# pads.net
KiCad netlist of a schematic drawn in EAGLE
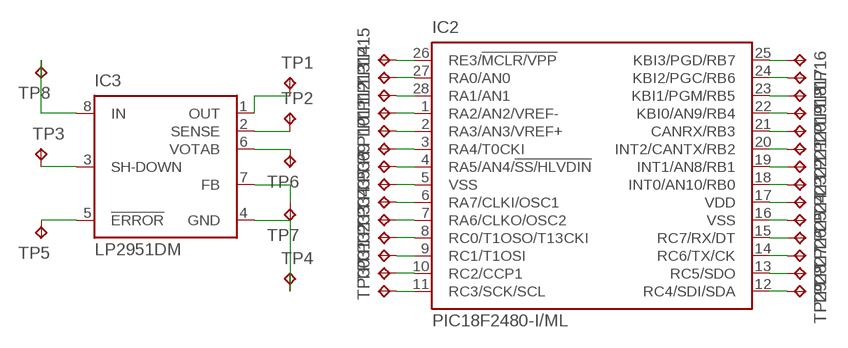
[diagram p0: schematic, sheet 1]

(export (version "E")
  (design (tool "Eeschema 10.0.6"))
  (components
    (comp (ref "IC2")
      (value "PIC18F2480-I/ML")
      (footprint "eagle-import:QFN28-ML_6X6MM")
      (fields (field (name "MF") "MICROCHIP"))
      (libsource (lib "eagle-import") (part "PIC18F280-I/ML4"))
    )
    (comp (ref "IC3")
      (value "LP2951DM")
      (footprint "eagle-import:MICRO8")
      (libsource (lib "eagle-import") (part "LP2951DM"))
    )
    (comp (ref "TP1")
      (value "TPPAD1-13Y")
      (footprint "eagle-import:P1-13Y")
      (libsource (lib "eagle-import") (part "TPPAD1-13Y"))
    )
    (comp (ref "TP2")
      (value "TPPAD1-13Y")
      (footprint "eagle-import:P1-13Y")
      (libsource (lib "eagle-import") (part "TPPAD1-13Y"))
    )
    (comp (ref "TP3")
      (value "TPPAD1-13Y")
      (footprint "eagle-import:P1-13Y")
      (libsource (lib "eagle-import") (part "TPPAD1-13Y"))
    )
    (comp (ref "TP4")
      (value "TPPAD1-13Y")
      (footprint "eagle-import:P1-13Y")
      (libsource (lib "eagle-import") (part "TPPAD1-13Y"))
    )
    (comp (ref "TP5")
      (value "TPPAD1-13Y")
      (footprint "eagle-import:P1-13Y")
      (libsource (lib "eagle-import") (part "TPPAD1-13Y"))
    )
    (comp (ref "TP6")
      (value "TPPAD1-13Y")
      (footprint "eagle-import:P1-13Y")
      (libsource (lib "eagle-import") (part "TPPAD1-13Y"))
    )
    (comp (ref "TP7")
      (value "TPPAD1-13Y")
      (footprint "eagle-import:P1-13Y")
      (libsource (lib "eagle-import") (part "TPPAD1-13Y"))
    )
    (comp (ref "TP8")
      (value "TPPAD1-13Y")
      (footprint "eagle-import:P1-13Y")
      (libsource (lib "eagle-import") (part "TPPAD1-13Y"))
    )
    (comp (ref "TP9")
      (value "TPPAD1-13Y")
      (footprint "eagle-import:P1-13Y")
      (libsource (lib "eagle-import") (part "TPPAD1-13Y"))
    )
    (comp (ref "TP10")
      (value "TPPAD1-13Y")
      (footprint "eagle-import:P1-13Y")
      (libsource (lib "eagle-import") (part "TPPAD1-13Y"))
    )
    (comp (ref "TP11")
      (value "TPPAD1-13Y")
      (footprint "eagle-import:P1-13Y")
      (libsource (lib "eagle-import") (part "TPPAD1-13Y"))
    )
    (comp (ref "TP12")
      (value "TPPAD1-13Y")
      (footprint "eagle-import:P1-13Y")
      (libsource (lib "eagle-import") (part "TPPAD1-13Y"))
    )
    (comp (ref "TP13")
      (value "TPPAD1-13Y")
      (footprint "eagle-import:P1-13Y")
      (libsource (lib "eagle-import") (part "TPPAD1-13Y"))
    )
    (comp (ref "TP14")
      (value "TPPAD1-13Y")
      (footprint "eagle-import:P1-13Y")
      (libsource (lib "eagle-import") (part "TPPAD1-13Y"))
    )
    (comp (ref "TP15")
      (value "TPPAD1-13Y")
      (footprint "eagle-import:P1-13Y")
      (libsource (lib "eagle-import") (part "TPPAD1-13Y"))
    )
    (comp (ref "TP16")
      (value "TPPAD1-13Y")
      (footprint "eagle-import:P1-13Y")
      (libsource (lib "eagle-import") (part "TPPAD1-13Y"))
    )
    (comp (ref "TP17")
      (value "TPPAD1-13Y")
      (footprint "eagle-import:P1-13Y")
      (libsource (lib "eagle-import") (part "TPPAD1-13Y"))
    )
    (comp (ref "TP18")
      (value "TPPAD1-13Y")
      (footprint "eagle-import:P1-13Y")
      (libsource (lib "eagle-import") (part "TPPAD1-13Y"))
    )
    (comp (ref "TP19")
      (value "TPPAD1-13Y")
      (footprint "eagle-import:P1-13Y")
      (libsource (lib "eagle-import") (part "TPPAD1-13Y"))
    )
    (comp (ref "TP20")
      (value "TPPAD1-13Y")
      (footprint "eagle-import:P1-13Y")
      (libsource (lib "eagle-import") (part "TPPAD1-13Y"))
    )
    (comp (ref "TP21")
      (value "TPPAD1-13Y")
      (footprint "eagle-import:P1-13Y")
      (libsource (lib "eagle-import") (part "TPPAD1-13Y"))
    )
    (comp (ref "TP22")
      (value "TPPAD1-13Y")
      (footprint "eagle-import:P1-13Y")
      (libsource (lib "eagle-import") (part "TPPAD1-13Y"))
    )
    (comp (ref "TP23")
      (value "TPPAD1-13Y")
      (footprint "eagle-import:P1-13Y")
      (libsource (lib "eagle-import") (part "TPPAD1-13Y"))
    )
    (comp (ref "TP24")
      (value "TPPAD1-13Y")
      (footprint "eagle-import:P1-13Y")
      (libsource (lib "eagle-import") (part "TPPAD1-13Y"))
    )
    (comp (ref "TP25")
      (value "TPPAD1-13Y")
      (footprint "eagle-import:P1-13Y")
      (libsource (lib "eagle-import") (part "TPPAD1-13Y"))
    )
    (comp (ref "TP26")
      (value "TPPAD1-13Y")
      (footprint "eagle-import:P1-13Y")
      (libsource (lib "eagle-import") (part "TPPAD1-13Y"))
    )
    (comp (ref "TP27")
      (value "TPPAD1-13Y")
      (footprint "eagle-import:P1-13Y")
      (libsource (lib "eagle-import") (part "TPPAD1-13Y"))
    )
    (comp (ref "TP28")
      (value "TPPAD1-13Y")
      (footprint "eagle-import:P1-13Y")
      (libsource (lib "eagle-import") (part "TPPAD1-13Y"))
    )
    (comp (ref "TP29")
      (value "TPPAD1-13Y")
      (footprint "eagle-import:P1-13Y")
      (libsource (lib "eagle-import") (part "TPPAD1-13Y"))
    )
    (comp (ref "TP30")
      (value "TPPAD1-13Y")
      (footprint "eagle-import:P1-13Y")
      (libsource (lib "eagle-import") (part "TPPAD1-13Y"))
    )
    (comp (ref "TP31")
      (value "TPPAD1-13Y")
      (footprint "eagle-import:P1-13Y")
      (libsource (lib "eagle-import") (part "TPPAD1-13Y"))
    )
    (comp (ref "TP32")
      (value "TPPAD1-13Y")
      (footprint "eagle-import:P1-13Y")
      (libsource (lib "eagle-import") (part "TPPAD1-13Y"))
    )
    (comp (ref "TP33")
      (value "TPPAD1-13Y")
      (footprint "eagle-import:P1-13Y")
      (libsource (lib "eagle-import") (part "TPPAD1-13Y"))
    )
    (comp (ref "TP34")
      (value "TPPAD1-13Y")
      (footprint "eagle-import:P1-13Y")
      (libsource (lib "eagle-import") (part "TPPAD1-13Y"))
    )
    (comp (ref "TP35")
      (value "TPPAD1-13Y")
      (footprint "eagle-import:P1-13Y")
      (libsource (lib "eagle-import") (part "TPPAD1-13Y"))
    )
    (comp (ref "TP36")
      (value "TPPAD1-13Y")
      (footprint "eagle-import:P1-13Y")
      (libsource (lib "eagle-import") (part "TPPAD1-13Y"))
    )
  )
  (nets
    (net (code "1") (name "Net-(IC2-CANRX{slash}RB3)") (class "Default")
      (node (ref "IC2") (pin "21") (pinfunction "CANRX/RB3_21") (pintype "bidirectional"))
      (node (ref "TP20") (pin "TP") (pinfunction "TP_TP") (pintype "input"))
    )
    (net (code "2") (name "Net-(IC2-INT0{slash}AN10{slash}RB0)") (class "Default")
      (node (ref "IC2") (pin "18") (pinfunction "INT0/AN10/RB0_18") (pintype "bidirectional"))
      (node (ref "TP23") (pin "TP") (pinfunction "TP_TP") (pintype "input"))
    )
    (net (code "3") (name "Net-(IC2-INT1{slash}AN8{slash}RB1)") (class "Default")
      (node (ref "IC2") (pin "19") (pinfunction "INT1/AN8/RB1_19") (pintype "bidirectional"))
      (node (ref "TP22") (pin "TP") (pinfunction "TP_TP") (pintype "input"))
    )
    (net (code "4") (name "Net-(IC2-INT2{slash}CANTX{slash}RB2)") (class "Default")
      (node (ref "IC2") (pin "20") (pinfunction "INT2/CANTX/RB2_20") (pintype "bidirectional"))
      (node (ref "TP21") (pin "TP") (pinfunction "TP_TP") (pintype "input"))
    )
    (net (code "5") (name "Net-(IC2-KBI0{slash}AN9{slash}RB4)") (class "Default")
      (node (ref "IC2") (pin "22") (pinfunction "KBI0/AN9/RB4_22") (pintype "bidirectional"))
      (node (ref "TP19") (pin "TP") (pinfunction "TP_TP") (pintype "input"))
    )
    (net (code "6") (name "Net-(IC2-KBI1{slash}PGM{slash}RB5)") (class "Default")
      (node (ref "IC2") (pin "23") (pinfunction "KBI1/PGM/RB5_23") (pintype "bidirectional"))
      (node (ref "TP18") (pin "TP") (pinfunction "TP_TP") (pintype "input"))
    )
    (net (code "7") (name "Net-(IC2-KBI2{slash}PGC{slash}RB6)") (class "Default")
      (node (ref "IC2") (pin "24") (pinfunction "KBI2/PGC/RB6_24") (pintype "bidirectional"))
      (node (ref "TP17") (pin "TP") (pinfunction "TP_TP") (pintype "input"))
    )
    (net (code "8") (name "Net-(IC2-KBI3{slash}PGD{slash}RB7)") (class "Default")
      (node (ref "IC2") (pin "25") (pinfunction "KBI3/PGD/RB7_25") (pintype "bidirectional"))
      (node (ref "TP16") (pin "TP") (pinfunction "TP_TP") (pintype "input"))
    )
    (net (code "9") (name "Net-(IC2-RA0{slash}AN0)") (class "Default")
      (node (ref "IC2") (pin "27") (pinfunction "RA0/AN0_27") (pintype "bidirectional"))
      (node (ref "TP14") (pin "TP") (pinfunction "TP_TP") (pintype "input"))
    )
    (net (code "10") (name "Net-(IC2-RA1{slash}AN1)") (class "Default")
      (node (ref "IC2") (pin "28") (pinfunction "RA1/AN1_28") (pintype "bidirectional"))
      (node (ref "TP13") (pin "TP") (pinfunction "TP_TP") (pintype "input"))
    )
    (net (code "11") (name "Net-(IC2-RA2{slash}AN2{slash}VREF-)") (class "Default")
      (node (ref "IC2") (pin "1") (pinfunction "RA2/AN2/VREF-_1") (pintype "bidirectional"))
      (node (ref "TP12") (pin "TP") (pinfunction "TP_TP") (pintype "input"))
    )
    (net (code "12") (name "Net-(IC2-RA3{slash}AN3{slash}VREF+)") (class "Default")
      (node (ref "IC2") (pin "2") (pinfunction "RA3/AN3/VREF+_2") (pintype "bidirectional"))
      (node (ref "TP11") (pin "TP") (pinfunction "TP_TP") (pintype "input"))
    )
    (net (code "13") (name "Net-(IC2-RA4{slash}T0CKI)") (class "Default")
      (node (ref "IC2") (pin "3") (pinfunction "RA4/T0CKI_3") (pintype "bidirectional"))
      (node (ref "TP10") (pin "TP") (pinfunction "TP_TP") (pintype "input"))
    )
    (net (code "14") (name "Net-(IC2-RA5{slash}AN4{slash}~{SS{slash}HLVDIN})") (class "Default")
      (node (ref "IC2") (pin "4") (pinfunction "RA5/AN4/~{SS/HLVDIN}_4") (pintype "bidirectional"))
      (node (ref "TP9") (pin "TP") (pinfunction "TP_TP") (pintype "input"))
    )
    (net (code "15") (name "Net-(IC2-RA6{slash}CLKO{slash}OSC2)") (class "Default")
      (node (ref "IC2") (pin "7") (pinfunction "RA6/CLKO/OSC2_7") (pintype "output"))
      (node (ref "TP34") (pin "TP") (pinfunction "TP_TP") (pintype "input"))
    )
    (net (code "16") (name "Net-(IC2-RA7{slash}CLKI{slash}OSC1)") (class "Default")
      (node (ref "IC2") (pin "6") (pinfunction "RA7/CLKI/OSC1_6") (pintype "input"))
      (node (ref "TP35") (pin "TP") (pinfunction "TP_TP") (pintype "input"))
    )
    (net (code "17") (name "Net-(IC2-RC0{slash}T1OSO{slash}T13CKI)") (class "Default")
      (node (ref "IC2") (pin "8") (pinfunction "RC0/T1OSO/T13CKI_8") (pintype "bidirectional"))
      (node (ref "TP33") (pin "TP") (pinfunction "TP_TP") (pintype "input"))
    )
    (net (code "18") (name "Net-(IC2-RC1{slash}T1OSI)") (class "Default")
      (node (ref "IC2") (pin "9") (pinfunction "RC1/T1OSI_9") (pintype "bidirectional"))
      (node (ref "TP32") (pin "TP") (pinfunction "TP_TP") (pintype "input"))
    )
    (net (code "19") (name "Net-(IC2-RC2{slash}CCP1)") (class "Default")
      (node (ref "IC2") (pin "10") (pinfunction "RC2/CCP1_10") (pintype "bidirectional"))
      (node (ref "TP31") (pin "TP") (pinfunction "TP_TP") (pintype "input"))
    )
    (net (code "20") (name "Net-(IC2-RC3{slash}SCK{slash}SCL)") (class "Default")
      (node (ref "IC2") (pin "11") (pinfunction "RC3/SCK/SCL_11") (pintype "bidirectional"))
      (node (ref "TP30") (pin "TP") (pinfunction "TP_TP") (pintype "input"))
    )
    (net (code "21") (name "Net-(IC2-RC4{slash}SDI{slash}SDA)") (class "Default")
      (node (ref "IC2") (pin "12") (pinfunction "RC4/SDI/SDA_12") (pintype "bidirectional"))
      (node (ref "TP29") (pin "TP") (pinfunction "TP_TP") (pintype "input"))
    )
    (net (code "22") (name "Net-(IC2-RC5{slash}SDO)") (class "Default")
      (node (ref "IC2") (pin "13") (pinfunction "RC5/SDO_13") (pintype "bidirectional"))
      (node (ref "TP28") (pin "TP") (pinfunction "TP_TP") (pintype "input"))
    )
    (net (code "23") (name "Net-(IC2-RC6{slash}TX{slash}CK)") (class "Default")
      (node (ref "IC2") (pin "14") (pinfunction "RC6/TX/CK_14") (pintype "bidirectional"))
      (node (ref "TP27") (pin "TP") (pinfunction "TP_TP") (pintype "input"))
    )
    (net (code "24") (name "Net-(IC2-RC7{slash}RX{slash}DT)") (class "Default")
      (node (ref "IC2") (pin "15") (pinfunction "RC7/RX/DT_15") (pintype "bidirectional"))
      (node (ref "TP26") (pin "TP") (pinfunction "TP_TP") (pintype "input"))
    )
    (net (code "25") (name "Net-(IC2-RE3{slash}~{MCLR{slash}VPP})") (class "Default")
      (node (ref "IC2") (pin "26") (pinfunction "RE3/~{MCLR/VPP}_26") (pintype "input"))
      (node (ref "TP15") (pin "TP") (pinfunction "TP_TP") (pintype "input"))
    )
    (net (code "26") (name "Net-(IC2-VDD)") (class "Default")
      (node (ref "IC2") (pin "17") (pinfunction "VDD_17") (pintype "power_in"))
      (node (ref "TP24") (pin "TP") (pinfunction "TP_TP") (pintype "input"))
    )
    (net (code "27") (name "Net-(IC2-VSS-Pad5)") (class "Default")
      (node (ref "IC2") (pin "5") (pinfunction "VSS_5") (pintype "power_in"))
      (node (ref "TP36") (pin "TP") (pinfunction "TP_TP") (pintype "input"))
    )
    (net (code "28") (name "Net-(IC2-VSS-Pad16)") (class "Default")
      (node (ref "IC2") (pin "16") (pinfunction "VSS_16") (pintype "power_in"))
      (node (ref "TP25") (pin "TP") (pinfunction "TP_TP") (pintype "input"))
    )
    (net (code "29") (name "Net-(IC3-FB)") (class "Default")
      (node (ref "IC3") (pin "7") (pinfunction "FB_7") (pintype "input"))
      (node (ref "TP7") (pin "TP") (pinfunction "TP_TP") (pintype "input"))
    )
    (net (code "30") (name "Net-(IC3-GND)") (class "Default")
      (node (ref "IC3") (pin "4") (pinfunction "GND_4") (pintype "power_in"))
      (node (ref "TP4") (pin "TP") (pinfunction "TP_TP") (pintype "input"))
    )
    (net (code "31") (name "Net-(IC3-IN)") (class "Default")
      (node (ref "IC3") (pin "8") (pinfunction "IN_8") (pintype "input"))
      (node (ref "TP8") (pin "TP") (pinfunction "TP_TP") (pintype "input"))
    )
    (net (code "32") (name "Net-(IC3-OUT)") (class "Default")
      (node (ref "IC3") (pin "1") (pinfunction "OUT_1") (pintype "input"))
      (node (ref "TP1") (pin "TP") (pinfunction "TP_TP") (pintype "input"))
    )
    (net (code "33") (name "Net-(IC3-SENSE)") (class "Default")
      (node (ref "IC3") (pin "2") (pinfunction "SENSE_2") (pintype "input"))
      (node (ref "TP2") (pin "TP") (pinfunction "TP_TP") (pintype "input"))
    )
    (net (code "34") (name "Net-(IC3-SH-DOWN)") (class "Default")
      (node (ref "IC3") (pin "3") (pinfunction "SH-DOWN_3") (pintype "input"))
      (node (ref "TP3") (pin "TP") (pinfunction "TP_TP") (pintype "input"))
    )
    (net (code "35") (name "Net-(IC3-VOTAB)") (class "Default")
      (node (ref "IC3") (pin "6") (pinfunction "VOTAB_6") (pintype "passive"))
      (node (ref "TP6") (pin "TP") (pinfunction "TP_TP") (pintype "input"))
    )
    (net (code "36") (name "Net-(IC3-~{ERROR})") (class "Default")
      (node (ref "IC3") (pin "5") (pinfunction "~{ERROR}_5") (pintype "output"))
      (node (ref "TP5") (pin "TP") (pinfunction "TP_TP") (pintype "input"))
    )
  )
)
